# OUTPUT.net
KiCad netlist of a schematic drawn in Altium Designer
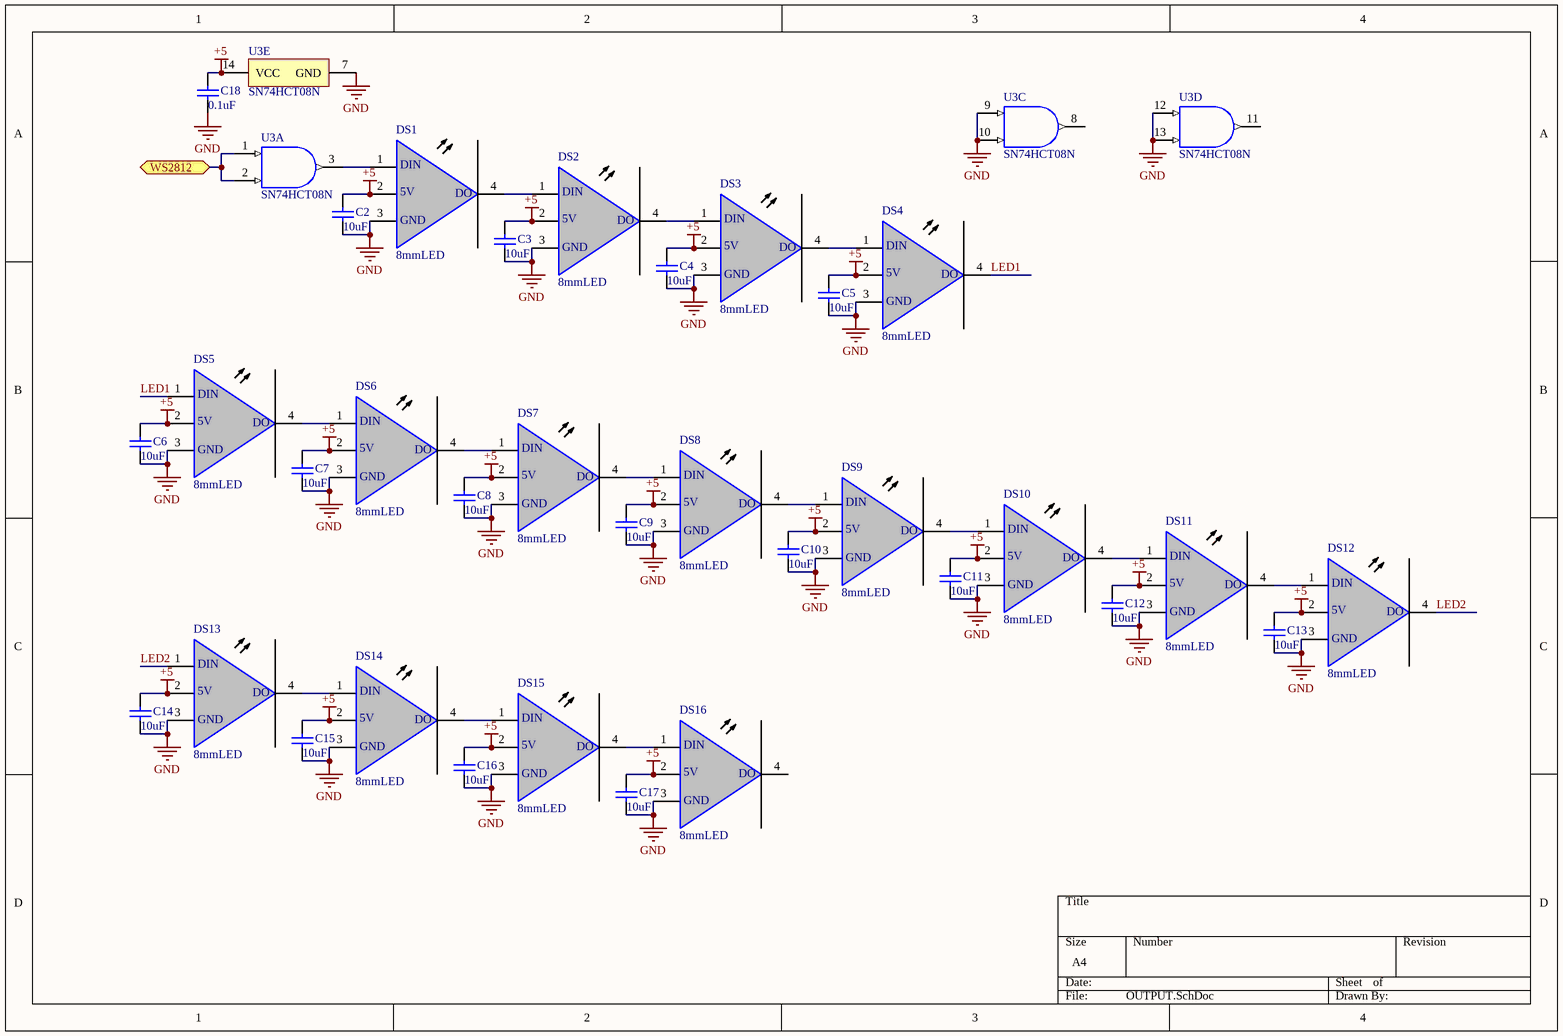
[diagram p0: OUTPUT.SchDoc]

(export (version "E")
  (design (tool "Eeschema 10.0.6"))
  (components
    (comp (ref "C2")
      (value "10uF")
      (footprint "CAPR51-254-508X318X736")
      (libsource (lib "Components - 05.08.25 - 01.44") (part "CMP-1664-00004-1"))
    )
    (comp (ref "C3")
      (value "10uF")
      (footprint "CAPR51-254-508X318X736")
      (libsource (lib "Components - 05.08.25 - 01.44") (part "CMP-1664-00004-1"))
    )
    (comp (ref "C4")
      (value "10uF")
      (footprint "CAPR51-254-508X318X736")
      (libsource (lib "Components - 05.08.25 - 01.44") (part "CMP-1664-00004-1"))
    )
    (comp (ref "C5")
      (value "10uF")
      (footprint "CAPR51-254-508X318X736")
      (libsource (lib "Components - 05.08.25 - 01.44") (part "CMP-1664-00004-1"))
    )
    (comp (ref "C6")
      (value "10uF")
      (footprint "CAPR51-254-508X318X736")
      (libsource (lib "Components - 05.08.25 - 01.44") (part "CMP-1664-00004-1"))
    )
    (comp (ref "C7")
      (value "10uF")
      (footprint "CAPR51-254-508X318X736")
      (libsource (lib "Components - 05.08.25 - 01.44") (part "CMP-1664-00004-1"))
    )
    (comp (ref "C8")
      (value "10uF")
      (footprint "CAPR51-254-508X318X736")
      (libsource (lib "Components - 05.08.25 - 01.44") (part "CMP-1664-00004-1"))
    )
    (comp (ref "C9")
      (value "10uF")
      (footprint "CAPR51-254-508X318X736")
      (libsource (lib "Components - 05.08.25 - 01.44") (part "CMP-1664-00004-1"))
    )
    (comp (ref "C10")
      (value "10uF")
      (footprint "CAPR51-254-508X318X736")
      (libsource (lib "Components - 05.08.25 - 01.44") (part "CMP-1664-00004-1"))
    )
    (comp (ref "C11")
      (value "10uF")
      (footprint "CAPR51-254-508X318X736")
      (libsource (lib "Components - 05.08.25 - 01.44") (part "CMP-1664-00004-1"))
    )
    (comp (ref "C12")
      (value "10uF")
      (footprint "CAPR51-254-508X318X736")
      (libsource (lib "Components - 05.08.25 - 01.44") (part "CMP-1664-00004-1"))
    )
    (comp (ref "C13")
      (value "10uF")
      (footprint "CAPR51-254-508X318X736")
      (libsource (lib "Components - 05.08.25 - 01.44") (part "CMP-1664-00004-1"))
    )
    (comp (ref "C14")
      (value "10uF")
      (footprint "CAPR51-254-508X318X736")
      (libsource (lib "Components - 05.08.25 - 01.44") (part "CMP-1664-00004-1"))
    )
    (comp (ref "C15")
      (value "10uF")
      (footprint "CAPR51-254-508X318X736")
      (libsource (lib "Components - 05.08.25 - 01.44") (part "CMP-1664-00004-1"))
    )
    (comp (ref "C16")
      (value "10uF")
      (footprint "CAPR51-254-508X318X736")
      (libsource (lib "Components - 05.08.25 - 01.44") (part "CMP-1664-00004-1"))
    )
    (comp (ref "C17")
      (value "10uF")
      (footprint "CAPR51-254-508X318X736")
      (libsource (lib "Components - 05.08.25 - 01.44") (part "CMP-1664-00004-1"))
    )
    (comp (ref "C18")
      (value "0.1uF")
      (footprint "CAPR51-254-508X318X736")
      (libsource (lib "Components - 05.08.25 - 01.44") (part "CMP-1664-00004-1"))
    )
    (comp (ref "DS1")
      (value "8mmLED")
      (footprint "8mm")
      (description "WS2812")
      (libsource (lib "8mmLED") (part "8mmLED"))
    )
    (comp (ref "DS2")
      (value "8mmLED")
      (footprint "8mm")
      (description "WS2812")
      (libsource (lib "8mmLED") (part "8mmLED"))
    )
    (comp (ref "DS3")
      (value "8mmLED")
      (footprint "8mm")
      (description "WS2812")
      (libsource (lib "8mmLED") (part "8mmLED"))
    )
    (comp (ref "DS4")
      (value "8mmLED")
      (footprint "8mm")
      (description "WS2812")
      (libsource (lib "8mmLED") (part "8mmLED"))
    )
    (comp (ref "DS5")
      (value "8mmLED")
      (footprint "8mm")
      (description "WS2812")
      (libsource (lib "8mmLED") (part "8mmLED"))
    )
    (comp (ref "DS6")
      (value "8mmLED")
      (footprint "8mm")
      (description "WS2812")
      (libsource (lib "8mmLED") (part "8mmLED"))
    )
    (comp (ref "DS7")
      (value "8mmLED")
      (footprint "8mm")
      (description "WS2812")
      (libsource (lib "8mmLED") (part "8mmLED"))
    )
    (comp (ref "DS8")
      (value "8mmLED")
      (footprint "8mm")
      (description "WS2812")
      (libsource (lib "8mmLED") (part "8mmLED"))
    )
    (comp (ref "DS9")
      (value "8mmLED")
      (footprint "8mm")
      (description "WS2812")
      (libsource (lib "8mmLED") (part "8mmLED"))
    )
    (comp (ref "DS10")
      (value "8mmLED")
      (footprint "8mm")
      (description "WS2812")
      (libsource (lib "8mmLED") (part "8mmLED"))
    )
    (comp (ref "DS11")
      (value "8mmLED")
      (footprint "8mm")
      (description "WS2812")
      (libsource (lib "8mmLED") (part "8mmLED"))
    )
    (comp (ref "DS12")
      (value "8mmLED")
      (footprint "8mm")
      (description "WS2812")
      (libsource (lib "8mmLED") (part "8mmLED"))
    )
    (comp (ref "DS13")
      (value "8mmLED")
      (footprint "8mm")
      (description "WS2812")
      (libsource (lib "8mmLED") (part "8mmLED"))
    )
    (comp (ref "DS14")
      (value "8mmLED")
      (footprint "8mm")
      (description "WS2812")
      (libsource (lib "8mmLED") (part "8mmLED"))
    )
    (comp (ref "DS15")
      (value "8mmLED")
      (footprint "8mm")
      (description "WS2812")
      (libsource (lib "8mmLED") (part "8mmLED"))
    )
    (comp (ref "DS16")
      (value "8mmLED")
      (footprint "8mm")
      (description "WS2812")
      (libsource (lib "8mmLED") (part "8mmLED"))
    )
    (comp (ref "U3")
      (value "SN74HCT08N")
      (footprint "N0014A")
      (description "Quadruple 2-Input Positive-AND Gates, N0014A, TUBE")
      (fields
        (field (name "MANUFACTURER") "Texas Instruments")
        (field (name "GENERIC PART NUMBER") "SN74HCT08")
      )
      (libsource (lib "Components - 05.08.25 - 14.49") (part "CMP-0777-00257-3"))
    )
  )
  (nets
    (net (code "1") (name "+5") (class "Default")
      (node (ref "C10") (pin "2") (pinfunction "2_2") (pintype "passive"))
      (node (ref "C11") (pin "2") (pinfunction "2_2") (pintype "passive"))
      (node (ref "C12") (pin "2") (pinfunction "2_2") (pintype "passive"))
      (node (ref "C13") (pin "2") (pinfunction "2_2") (pintype "passive"))
      (node (ref "C14") (pin "2") (pinfunction "2_2") (pintype "passive"))
      (node (ref "C15") (pin "2") (pinfunction "2_2") (pintype "passive"))
      (node (ref "C16") (pin "2") (pinfunction "2_2") (pintype "passive"))
      (node (ref "C17") (pin "2") (pinfunction "2_2") (pintype "passive"))
      (node (ref "C18") (pin "2") (pinfunction "2_2") (pintype "passive"))
      (node (ref "C2") (pin "2") (pinfunction "2_2") (pintype "passive"))
      (node (ref "C3") (pin "2") (pinfunction "2_2") (pintype "passive"))
      (node (ref "C4") (pin "2") (pinfunction "2_2") (pintype "passive"))
      (node (ref "C5") (pin "2") (pinfunction "2_2") (pintype "passive"))
      (node (ref "C6") (pin "2") (pinfunction "2_2") (pintype "passive"))
      (node (ref "C7") (pin "2") (pinfunction "2_2") (pintype "passive"))
      (node (ref "C8") (pin "2") (pinfunction "2_2") (pintype "passive"))
      (node (ref "C9") (pin "2") (pinfunction "2_2") (pintype "passive"))
      (node (ref "DS1") (pin "2") (pinfunction "CATHODE_2") (pintype "passive"))
      (node (ref "DS10") (pin "2") (pinfunction "CATHODE_2") (pintype "passive"))
      (node (ref "DS11") (pin "2") (pinfunction "CATHODE_2") (pintype "passive"))
      (node (ref "DS12") (pin "2") (pinfunction "CATHODE_2") (pintype "passive"))
      (node (ref "DS13") (pin "2") (pinfunction "CATHODE_2") (pintype "passive"))
      (node (ref "DS14") (pin "2") (pinfunction "CATHODE_2") (pintype "passive"))
      (node (ref "DS15") (pin "2") (pinfunction "CATHODE_2") (pintype "passive"))
      (node (ref "DS16") (pin "2") (pinfunction "CATHODE_2") (pintype "passive"))
      (node (ref "DS2") (pin "2") (pinfunction "CATHODE_2") (pintype "passive"))
      (node (ref "DS3") (pin "2") (pinfunction "CATHODE_2") (pintype "passive"))
      (node (ref "DS4") (pin "2") (pinfunction "CATHODE_2") (pintype "passive"))
      (node (ref "DS5") (pin "2") (pinfunction "CATHODE_2") (pintype "passive"))
      (node (ref "DS6") (pin "2") (pinfunction "CATHODE_2") (pintype "passive"))
      (node (ref "DS7") (pin "2") (pinfunction "CATHODE_2") (pintype "passive"))
      (node (ref "DS8") (pin "2") (pinfunction "CATHODE_2") (pintype "passive"))
      (node (ref "DS9") (pin "2") (pinfunction "CATHODE_2") (pintype "passive"))
      (node (ref "U3") (pin "14") (pinfunction "VCC_14") (pintype "power_in"))
    )
    (net (code "2") (name "/LED1") (class "Default")
      (node (ref "DS4") (pin "4") (pinfunction "GREEN_4") (pintype "passive"))
      (node (ref "DS5") (pin "1") (pinfunction "RED_1") (pintype "passive"))
    )
    (net (code "3") (name "/LED2") (class "Default")
      (node (ref "DS12") (pin "4") (pinfunction "GREEN_4") (pintype "passive"))
      (node (ref "DS13") (pin "1") (pinfunction "RED_1") (pintype "passive"))
    )
    (net (code "4") (name "/WS2812") (class "Default")
      (node (ref "U3") (pin "1") (pinfunction "1A_1") (pintype "input"))
      (node (ref "U3") (pin "2") (pinfunction "1B_2") (pintype "input"))
    )
    (net (code "5") (name "GND") (class "Default")
      (node (ref "C10") (pin "1") (pinfunction "1_1") (pintype "passive"))
      (node (ref "C11") (pin "1") (pinfunction "1_1") (pintype "passive"))
      (node (ref "C12") (pin "1") (pinfunction "1_1") (pintype "passive"))
      (node (ref "C13") (pin "1") (pinfunction "1_1") (pintype "passive"))
      (node (ref "C14") (pin "1") (pinfunction "1_1") (pintype "passive"))
      (node (ref "C15") (pin "1") (pinfunction "1_1") (pintype "passive"))
      (node (ref "C16") (pin "1") (pinfunction "1_1") (pintype "passive"))
      (node (ref "C17") (pin "1") (pinfunction "1_1") (pintype "passive"))
      (node (ref "C18") (pin "1") (pinfunction "1_1") (pintype "passive"))
      (node (ref "C2") (pin "1") (pinfunction "1_1") (pintype "passive"))
      (node (ref "C3") (pin "1") (pinfunction "1_1") (pintype "passive"))
      (node (ref "C4") (pin "1") (pinfunction "1_1") (pintype "passive"))
      (node (ref "C5") (pin "1") (pinfunction "1_1") (pintype "passive"))
      (node (ref "C6") (pin "1") (pinfunction "1_1") (pintype "passive"))
      (node (ref "C7") (pin "1") (pinfunction "1_1") (pintype "passive"))
      (node (ref "C8") (pin "1") (pinfunction "1_1") (pintype "passive"))
      (node (ref "C9") (pin "1") (pinfunction "1_1") (pintype "passive"))
      (node (ref "DS1") (pin "3") (pinfunction "BLUE_3") (pintype "passive"))
      (node (ref "DS10") (pin "3") (pinfunction "BLUE_3") (pintype "passive"))
      (node (ref "DS11") (pin "3") (pinfunction "BLUE_3") (pintype "passive"))
      (node (ref "DS12") (pin "3") (pinfunction "BLUE_3") (pintype "passive"))
      (node (ref "DS13") (pin "3") (pinfunction "BLUE_3") (pintype "passive"))
      (node (ref "DS14") (pin "3") (pinfunction "BLUE_3") (pintype "passive"))
      (node (ref "DS15") (pin "3") (pinfunction "BLUE_3") (pintype "passive"))
      (node (ref "DS16") (pin "3") (pinfunction "BLUE_3") (pintype "passive"))
      (node (ref "DS2") (pin "3") (pinfunction "BLUE_3") (pintype "passive"))
      (node (ref "DS3") (pin "3") (pinfunction "BLUE_3") (pintype "passive"))
      (node (ref "DS4") (pin "3") (pinfunction "BLUE_3") (pintype "passive"))
      (node (ref "DS5") (pin "3") (pinfunction "BLUE_3") (pintype "passive"))
      (node (ref "DS6") (pin "3") (pinfunction "BLUE_3") (pintype "passive"))
      (node (ref "DS7") (pin "3") (pinfunction "BLUE_3") (pintype "passive"))
      (node (ref "DS8") (pin "3") (pinfunction "BLUE_3") (pintype "passive"))
      (node (ref "DS9") (pin "3") (pinfunction "BLUE_3") (pintype "passive"))
      (node (ref "U3") (pin "10") (pinfunction "3B_10") (pintype "input"))
      (node (ref "U3") (pin "12") (pinfunction "4A_12") (pintype "input"))
      (node (ref "U3") (pin "13") (pinfunction "4B_13") (pintype "input"))
      (node (ref "U3") (pin "7") (pinfunction "GND_7") (pintype "power_in"))
      (node (ref "U3") (pin "9") (pinfunction "3A_9") (pintype "input"))
    )
    (net (code "6") (name "Net-(DS1-GREEN)") (class "Default")
      (node (ref "DS1") (pin "4") (pinfunction "GREEN_4") (pintype "passive"))
      (node (ref "DS2") (pin "1") (pinfunction "RED_1") (pintype "passive"))
    )
    (net (code "7") (name "Net-(DS1-RED)") (class "Default")
      (node (ref "DS1") (pin "1") (pinfunction "RED_1") (pintype "passive"))
      (node (ref "U3") (pin "3") (pinfunction "1Y_3") (pintype "output"))
    )
    (net (code "8") (name "Net-(DS2-GREEN)") (class "Default")
      (node (ref "DS2") (pin "4") (pinfunction "GREEN_4") (pintype "passive"))
      (node (ref "DS3") (pin "1") (pinfunction "RED_1") (pintype "passive"))
    )
    (net (code "9") (name "Net-(DS3-GREEN)") (class "Default")
      (node (ref "DS3") (pin "4") (pinfunction "GREEN_4") (pintype "passive"))
      (node (ref "DS4") (pin "1") (pinfunction "RED_1") (pintype "passive"))
    )
    (net (code "10") (name "Net-(DS5-GREEN)") (class "Default")
      (node (ref "DS5") (pin "4") (pinfunction "GREEN_4") (pintype "passive"))
      (node (ref "DS6") (pin "1") (pinfunction "RED_1") (pintype "passive"))
    )
    (net (code "11") (name "Net-(DS6-GREEN)") (class "Default")
      (node (ref "DS6") (pin "4") (pinfunction "GREEN_4") (pintype "passive"))
      (node (ref "DS7") (pin "1") (pinfunction "RED_1") (pintype "passive"))
    )
    (net (code "12") (name "Net-(DS7-GREEN)") (class "Default")
      (node (ref "DS7") (pin "4") (pinfunction "GREEN_4") (pintype "passive"))
      (node (ref "DS8") (pin "1") (pinfunction "RED_1") (pintype "passive"))
    )
    (net (code "13") (name "Net-(DS8-GREEN)") (class "Default")
      (node (ref "DS8") (pin "4") (pinfunction "GREEN_4") (pintype "passive"))
      (node (ref "DS9") (pin "1") (pinfunction "RED_1") (pintype "passive"))
    )
    (net (code "14") (name "Net-(DS10-GREEN)") (class "Default")
      (node (ref "DS10") (pin "4") (pinfunction "GREEN_4") (pintype "passive"))
      (node (ref "DS11") (pin "1") (pinfunction "RED_1") (pintype "passive"))
    )
    (net (code "15") (name "Net-(DS10-RED)") (class "Default")
      (node (ref "DS10") (pin "1") (pinfunction "RED_1") (pintype "passive"))
      (node (ref "DS9") (pin "4") (pinfunction "GREEN_4") (pintype "passive"))
    )
    (net (code "16") (name "Net-(DS11-GREEN)") (class "Default")
      (node (ref "DS11") (pin "4") (pinfunction "GREEN_4") (pintype "passive"))
      (node (ref "DS12") (pin "1") (pinfunction "RED_1") (pintype "passive"))
    )
    (net (code "17") (name "Net-(DS13-GREEN)") (class "Default")
      (node (ref "DS13") (pin "4") (pinfunction "GREEN_4") (pintype "passive"))
      (node (ref "DS14") (pin "1") (pinfunction "RED_1") (pintype "passive"))
    )
    (net (code "18") (name "Net-(DS14-GREEN)") (class "Default")
      (node (ref "DS14") (pin "4") (pinfunction "GREEN_4") (pintype "passive"))
      (node (ref "DS15") (pin "1") (pinfunction "RED_1") (pintype "passive"))
    )
    (net (code "19") (name "Net-(DS15-GREEN)") (class "Default")
      (node (ref "DS15") (pin "4") (pinfunction "GREEN_4") (pintype "passive"))
      (node (ref "DS16") (pin "1") (pinfunction "RED_1") (pintype "passive"))
    )
    (net (code "20") (name "unconnected-(DS16-GREEN-Pad4)") (class "Default")
      (node (ref "DS16") (pin "4") (pinfunction "GREEN_4") (pintype "passive"))
    )
    (net (code "21") (name "unconnected-(U3C-3Y-Pad8)") (class "Default")
      (node (ref "U3") (pin "8") (pinfunction "3Y_8") (pintype "output"))
    )
    (net (code "22") (name "unconnected-(U3D-4Y-Pad11)") (class "Default")
      (node (ref "U3") (pin "11") (pinfunction "4Y_11") (pintype "output"))
    )
  )
)
